# MCU.net
KiCad netlist of a schematic drawn in Altium Designer
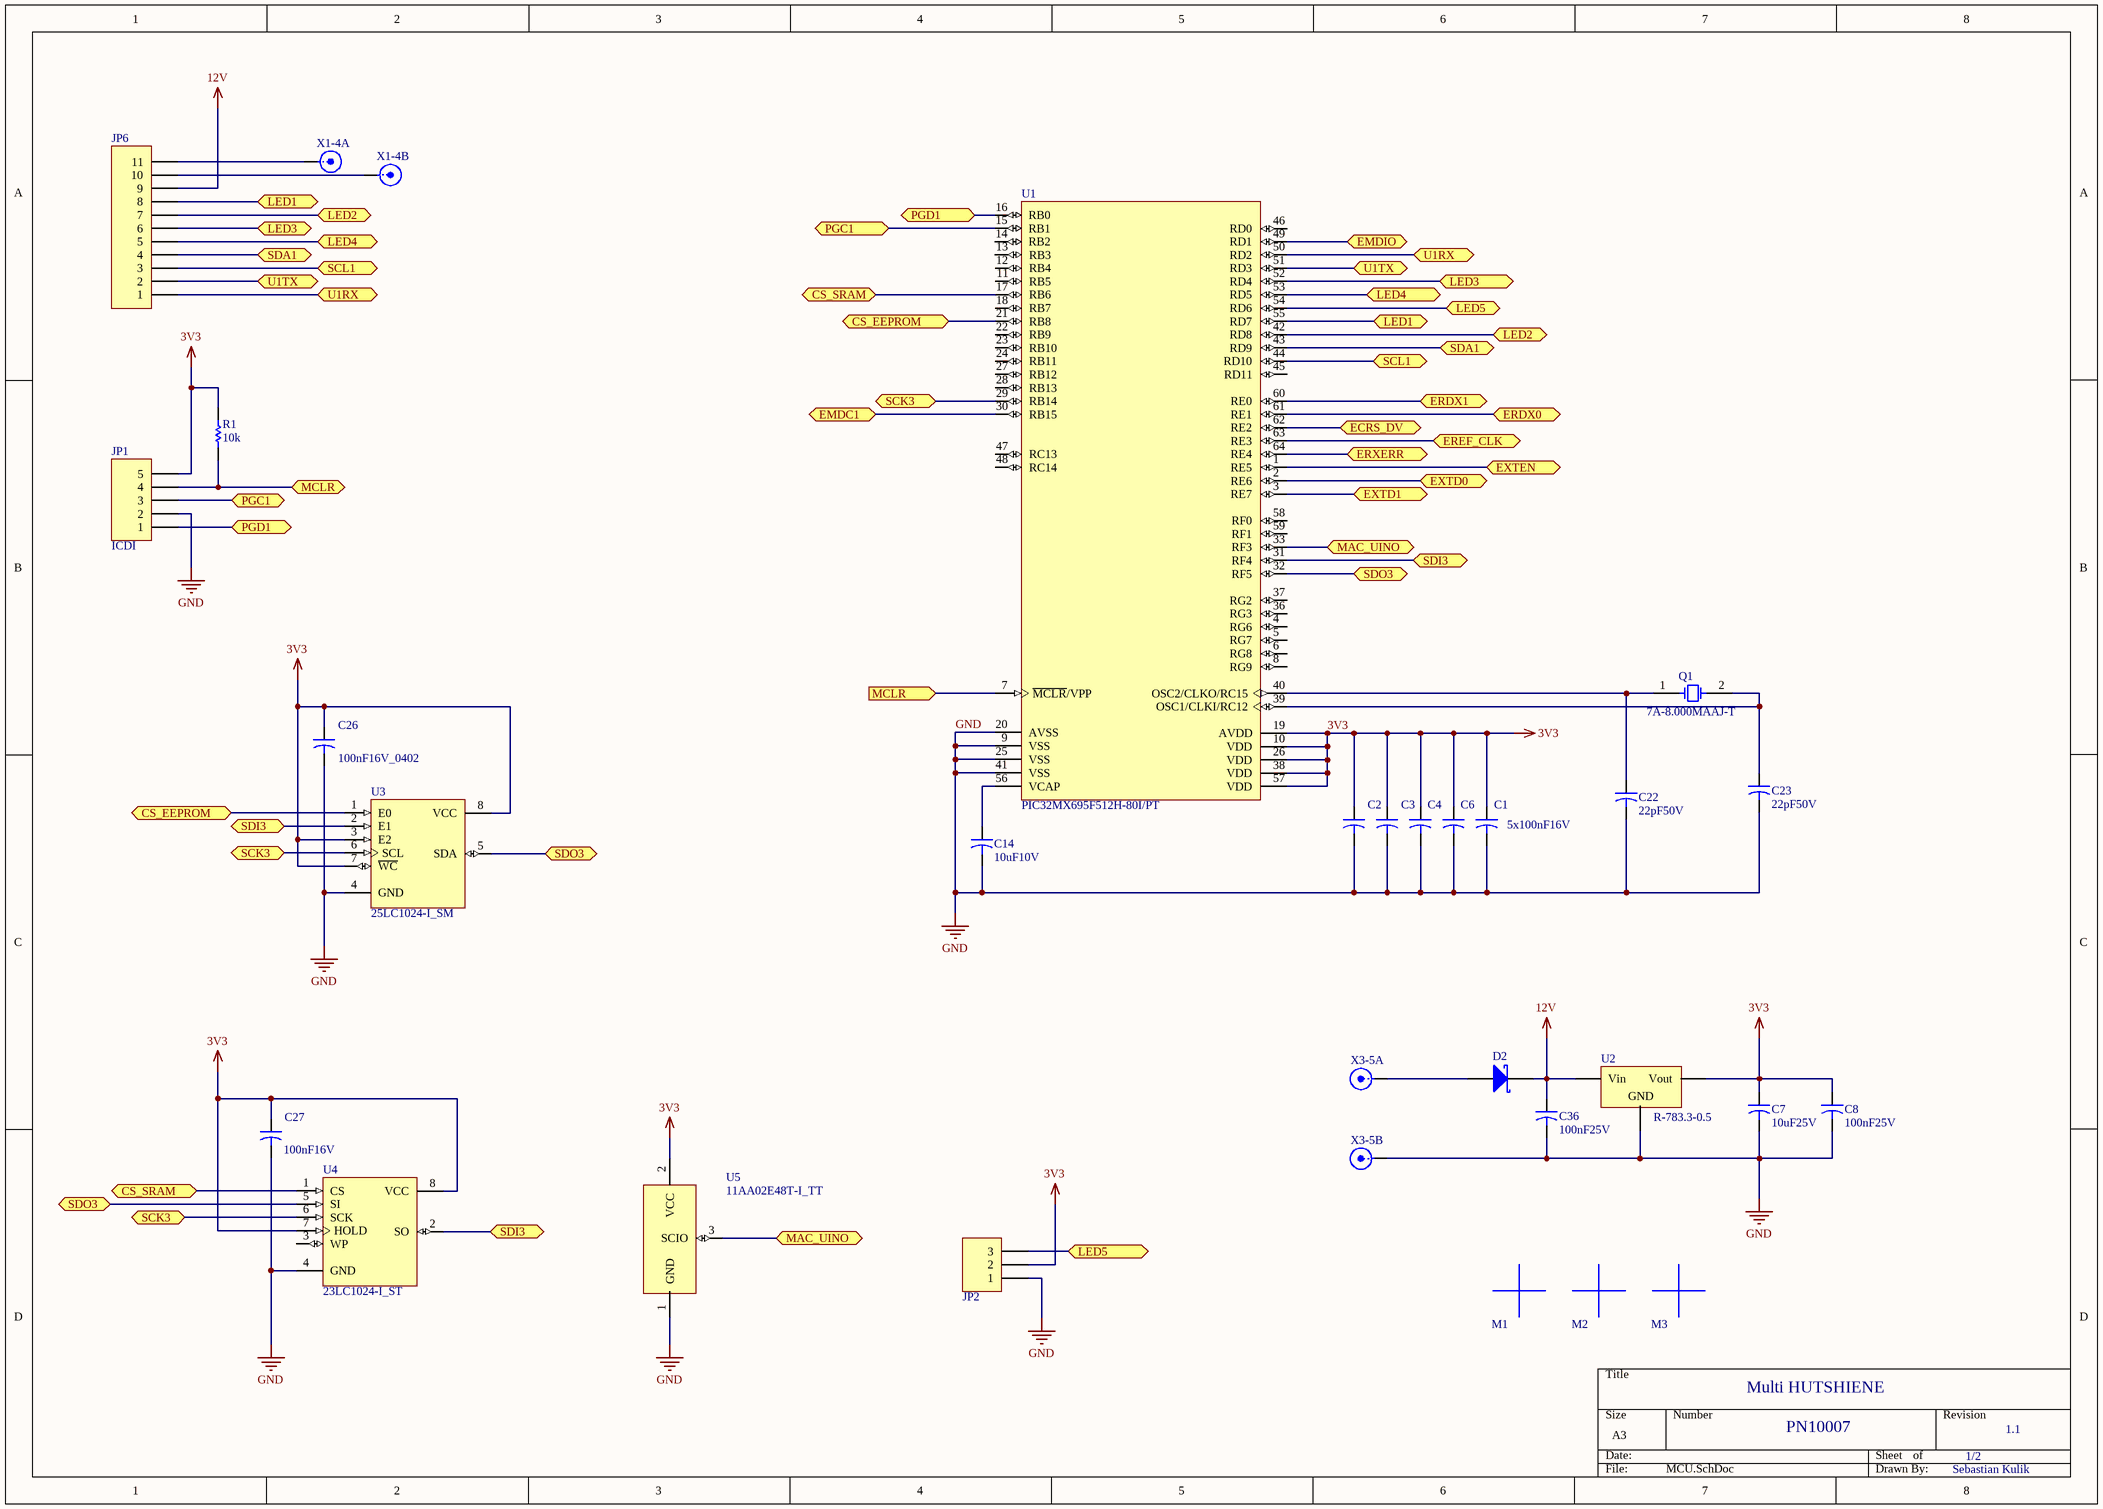
[diagram p0: MCU.SchDoc]

(export (version "E")
  (design (tool "Eeschema 10.0.6"))
  (components
    (comp (ref "C1")
      (value "100nF16V_0402")
      (footprint "C0402")
      (description "Capacitor")
      (fields (field (name "MANUFACTURER") "TDK") (field (name "PUBLISHER") "Sebastian Kulik"))
      (libsource (lib "Capacitors") (part "100nF16V_0402"))
    )
    (comp (ref "C2")
      (value "100nF16V_0402")
      (footprint "C0402")
      (description "Capacitor")
      (fields (field (name "MANUFACTURER") "TDK") (field (name "PUBLISHER") "Sebastian Kulik"))
      (libsource (lib "Capacitors") (part "100nF16V_0402"))
    )
    (comp (ref "C3")
      (value "100nF16V_0402")
      (footprint "C0402")
      (description "Capacitor")
      (fields (field (name "MANUFACTURER") "TDK") (field (name "PUBLISHER") "Sebastian Kulik"))
      (libsource (lib "Capacitors") (part "100nF16V_0402"))
    )
    (comp (ref "C4")
      (value "100nF16V_0402")
      (footprint "C0402")
      (description "Capacitor")
      (fields (field (name "MANUFACTURER") "TDK") (field (name "PUBLISHER") "Sebastian Kulik"))
      (libsource (lib "Capacitors") (part "100nF16V_0402"))
    )
    (comp (ref "C6")
      (value "100nF16V_0402")
      (footprint "C0402")
      (description "Capacitor")
      (fields (field (name "MANUFACTURER") "TDK") (field (name "PUBLISHER") "Sebastian Kulik"))
      (libsource (lib "Capacitors") (part "100nF16V_0402"))
    )
    (comp (ref "C7")
      (value "10uF25V")
      (footprint "C1210")
      (description "Capacitor")
      (fields
        (field (name "MANUFACTURER") "TDK")
        (field (name "Comment") "10uF25V_1210")
        (field (name "PUBLISHER") "Sebastian Kulik")
      )
      (libsource (lib "Capacitors") (part "10uF25V_1210"))
    )
    (comp (ref "C8")
      (value "100nF25V")
      (footprint "C0402")
      (description "AVX, X5R, 10%, 25V")
      (fields
        (field (name "MANUFACTURER") "AVX")
        (field (name "Comment") "100nF25V_0402")
        (field (name "PUBLISHER") "Sebastian Kulik")
      )
      (libsource (lib "Capacitors") (part "100nF25V_0402"))
    )
    (comp (ref "C14")
      (value "10uF10V")
      (footprint "C0603")
      (description "Capacitor")
      (fields
        (field (name "MANUFACTURER") "AVX")
        (field (name "Comment") "10uF10V_0603")
        (field (name "PUBLISHER") "Sebastian Kulik")
      )
      (libsource (lib "Capacitors") (part "10uF10V_0603"))
    )
    (comp (ref "C22")
      (value "22pF50V")
      (footprint "C0402")
      (description "Murata, GRM series, 50V")
      (fields
        (field (name "MANUFACTURER") "Murata")
        (field (name "Comment") "22pF50V_0402")
        (field (name "PUBLISHER") "Sebastian Kulik")
      )
      (libsource (lib "Capacitors") (part "22pF50V_0402"))
    )
    (comp (ref "C23")
      (value "22pF50V")
      (footprint "C0402")
      (description "Murata, GRM series, 50V")
      (fields
        (field (name "MANUFACTURER") "Murata")
        (field (name "Comment") "22pF50V_0402")
        (field (name "PUBLISHER") "Sebastian Kulik")
      )
      (libsource (lib "Capacitors") (part "22pF50V_0402"))
    )
    (comp (ref "C26")
      (value "100nF16V_0402")
      (footprint "C0402")
      (description "Capacitor")
      (fields (field (name "MANUFACTURER") "TDK") (field (name "PUBLISHER") "Sebastian Kulik"))
      (libsource (lib "Capacitors") (part "100nF16V_0402"))
    )
    (comp (ref "C27")
      (value "100nF16V")
      (footprint "C0402")
      (description "Capacitor")
      (fields
        (field (name "MANUFACTURER") "TDK")
        (field (name "Comment") "100nF16V_0402")
        (field (name "PUBLISHER") "Sebastian Kulik")
      )
      (libsource (lib "Capacitors") (part "100nF16V_0402"))
    )
    (comp (ref "C36")
      (value "100nF25V")
      (footprint "C0402")
      (description "AVX, X5R, 10%, 25V")
      (fields
        (field (name "MANUFACTURER") "AVX")
        (field (name "Comment") "100nF25V_0402")
        (field (name "PUBLISHER") "Sebastian Kulik")
      )
      (libsource (lib "Capacitors") (part "100nF25V_0402"))
    )
    (comp (ref "D2")
      (value "SD103AW-V-GS08")
      (footprint "SOD123")
      (description "Diode Schottky,2A,40V")
      (fields (field (name "MANUFACTURER") "Vishay") (field (name "PUBLISHER") "Sebastian Kulik"))
      (libsource (lib "Discrete") (part "SD103AW-V-GS08"))
    )
    (comp (ref "JP1")
      (value "ICDI")
      (footprint "HDR1X5-1.27")
      (description "Header, 5-Pin")
      (fields (field (name "PUBLISHER") "Sebastian Kulik"))
      (libsource (lib "Connectors") (part "ICDI"))
    )
    (comp (ref "JP2")
      (value "Header-3")
      (footprint "HDR1X3")
      (description "Header-3-Pin")
      (fields (field (name "PUBLISHER") "Sebastian Kulik"))
      (libsource (lib "Connectors") (part "Header-3"))
    )
    (comp (ref "JP6")
      (value "Header 11_2.54")
      (footprint "HDR1X11_2.54")
      (description "Header, 11-Pin")
      (fields (field (name "PUBLISHER") "Altium Limited"))
      (libsource (lib "Connectors") (part "Header 11_2.54"))
    )
    (comp (ref "M1") (value "Mark") (footprint "Mark-3mm") (libsource (lib "Symbols") (part "Mark")))
    (comp (ref "M2") (value "Mark") (footprint "Mark-3mm") (libsource (lib "Symbols") (part "Mark")))
    (comp (ref "M3") (value "Mark") (footprint "Mark-3mm") (libsource (lib "Symbols") (part "Mark")))
    (comp (ref "Q1")
      (value "7A-8.000MAAJ-T")
      (footprint "TXC_7A")
      (description "Crystal, 7A-8.000MAAJ-T")
      (fields (field (name "MANUFACTURER") "TXC") (field (name "PUBLISHER") "Sebastian Kulik"))
      (libsource (lib "Passives") (part "Crystal_8MHz"))
    )
    (comp (ref "R1")
      (value "10k")
      (footprint "R0402")
      (description "Vishay CRCW series, 125mW, 1%")
      (fields
        (field (name "MANUFACTURER") "Vishay")
        (field (name "Comment") "10k_0402")
        (field (name "PUBLISHER") "Sebastian Kulik")
      )
      (libsource (lib "Resistors") (part "10k_0402"))
    )
    (comp (ref "U1")
      (value "PIC32MX695F512H-80I/PT")
      (footprint "TQFP-64_N1")
      (fields (field (name "MANUFACTURER") "Microchip") (field (name "PUBLISHER") "Sebastian Kulik"))
      (libsource (lib "ICs") (part "PIC32MX695F512H-80I/PT"))
    )
    (comp (ref "U2")
      (value "R-783.3-0.5")
      (footprint "R-783_3-0_5")
      (description "Voltage Regulator")
      (fields (field (name "MANUFACTURER") "Recom") (field (name "PUBLISHER") "Sebastian Kulik"))
      (libsource (lib "ICs") (part "Recom-R-783_3-0_5"))
    )
    (comp (ref "U3")
      (value "25LC1024-I_SM")
      (footprint "SOP8_N")
      (description "1024 Kbit Serial SPI Bus EEPROM")
      (fields (field (name "MANUFACTURER") "Microchip") (field (name "PUBLISHER") "Sebastian Kulik"))
      (libsource (lib "ICs") (part "25LC1024-I_SM"))
    )
    (comp (ref "U4")
      (value "23LC1024-I_ST")
      (footprint "TSSOP8")
      (description "1 Mbit Serial  EEPROM")
      (fields (field (name "MANUFACTURER") "Microchip") (field (name "PUBLISHER") "Sebastian Kulik"))
      (libsource (lib "ICs") (part "23LC1024-I_ST"))
    )
    (comp (ref "U5")
      (value "11AA02E48T-I_TT")
      (footprint "SOT23_M")
      (description "2 kbit Serial  EEPROM")
      (fields (field (name "MANUFACTURER") "Microchip") (field (name "PUBLISHER") "Sebastian Kulik"))
      (libsource (lib "ICs") (part "11AA02E48T-I_TT"))
    )
    (comp (ref "X1-4")
      (value "Terminal-Wago_2")
      (footprint "WAGO-243-211")
      (description "Wago terminal-2")
      (fields (field (name "PUBLISHER") "Altium Limited"))
      (libsource (lib "Connectors") (part "Terminal-Wago_2"))
    )
    (comp (ref "X3-5")
      (value "Terminal-Wago_2")
      (footprint "WAGO-243-211")
      (description "Wago terminal-2")
      (fields (field (name "PUBLISHER") "Altium Limited"))
      (libsource (lib "") (part "Terminal-Wago_2_1"))
    )
  )
  (nets
    (net (code "1") (name "/CS_EEPROM") (class "Default")
      (node (ref "U1") (pin "21") (pinfunction "RB8_21") (pintype "bidirectional"))
      (node (ref "U3") (pin "1") (pinfunction "E0_1") (pintype "input"))
    )
    (net (code "2") (name "/CS_SRAM") (class "Default")
      (node (ref "U1") (pin "17") (pinfunction "RB6_17") (pintype "bidirectional"))
      (node (ref "U4") (pin "1") (pinfunction "CS_1") (pintype "input"))
    )
    (net (code "3") (name "/ECRS_DV") (class "Default")
      (node (ref "U1") (pin "62") (pinfunction "RE2_62") (pintype "bidirectional"))
    )
    (net (code "4") (name "/EMDC1") (class "Default")
      (node (ref "U1") (pin "30") (pinfunction "RB15_30") (pintype "bidirectional"))
    )
    (net (code "5") (name "/EMDIO") (class "Default")
      (node (ref "U1") (pin "49") (pinfunction "RD1_49") (pintype "bidirectional"))
    )
    (net (code "6") (name "/ERDX0") (class "Default")
      (node (ref "U1") (pin "61") (pinfunction "RE1_61") (pintype "bidirectional"))
    )
    (net (code "7") (name "/ERDX1") (class "Default")
      (node (ref "U1") (pin "60") (pinfunction "RE0_60") (pintype "bidirectional"))
    )
    (net (code "8") (name "/EREF_CLK") (class "Default")
      (node (ref "U1") (pin "63") (pinfunction "RE3_63") (pintype "bidirectional"))
    )
    (net (code "9") (name "/ERXERR") (class "Default")
      (node (ref "U1") (pin "64") (pinfunction "RE4_64") (pintype "bidirectional"))
    )
    (net (code "10") (name "/EXTD0") (class "Default")
      (node (ref "U1") (pin "2") (pinfunction "RE6_2") (pintype "bidirectional"))
    )
    (net (code "11") (name "/EXTD1") (class "Default")
      (node (ref "U1") (pin "3") (pinfunction "RE7_3") (pintype "bidirectional"))
    )
    (net (code "12") (name "/EXTEN") (class "Default")
      (node (ref "U1") (pin "1") (pinfunction "RE5_1") (pintype "bidirectional"))
    )
    (net (code "13") (name "/LED1") (class "Default")
      (node (ref "JP6") (pin "8") (pinfunction "8_8") (pintype "passive"))
      (node (ref "U1") (pin "55") (pinfunction "RD7_55") (pintype "bidirectional"))
    )
    (net (code "14") (name "/LED2") (class "Default")
      (node (ref "JP6") (pin "7") (pinfunction "7_7") (pintype "passive"))
      (node (ref "U1") (pin "42") (pinfunction "RD8_42") (pintype "bidirectional"))
    )
    (net (code "15") (name "/LED3") (class "Default")
      (node (ref "JP6") (pin "6") (pinfunction "6_6") (pintype "passive"))
      (node (ref "U1") (pin "52") (pinfunction "RD4_52") (pintype "bidirectional"))
    )
    (net (code "16") (name "/LED4") (class "Default")
      (node (ref "JP6") (pin "5") (pinfunction "5_5") (pintype "passive"))
      (node (ref "U1") (pin "53") (pinfunction "RD5_53") (pintype "bidirectional"))
    )
    (net (code "17") (name "/LED5") (class "Default")
      (node (ref "JP2") (pin "3") (pinfunction "3_3") (pintype "passive"))
      (node (ref "U1") (pin "54") (pinfunction "RD6_54") (pintype "bidirectional"))
    )
    (net (code "18") (name "/MAC_UINO") (class "Default")
      (node (ref "U1") (pin "33") (pinfunction "RF3_33") (pintype "bidirectional"))
      (node (ref "U5") (pin "3") (pinfunction "SCIO_3") (pintype "bidirectional"))
    )
    (net (code "19") (name "/MCLR") (class "Default")
      (node (ref "JP1") (pin "4") (pinfunction "4_4") (pintype "passive"))
      (node (ref "R1") (pin "1") (pinfunction "1_1") (pintype "passive"))
      (node (ref "U1") (pin "7") (pinfunction "~{MCLR}/VPP_7") (pintype "input"))
    )
    (net (code "20") (name "/PGC1") (class "Default")
      (node (ref "JP1") (pin "3") (pinfunction "3_3") (pintype "passive"))
      (node (ref "U1") (pin "15") (pinfunction "RB1_15") (pintype "bidirectional"))
    )
    (net (code "21") (name "/PGD1") (class "Default")
      (node (ref "JP1") (pin "1") (pinfunction "1_1") (pintype "passive"))
      (node (ref "U1") (pin "16") (pinfunction "RB0_16") (pintype "bidirectional"))
    )
    (net (code "22") (name "/SCK3") (class "Default")
      (node (ref "U1") (pin "29") (pinfunction "RB14_29") (pintype "bidirectional"))
      (node (ref "U3") (pin "6") (pinfunction "SCL_6") (pintype "input"))
      (node (ref "U4") (pin "6") (pinfunction "SCK_6") (pintype "input"))
    )
    (net (code "23") (name "/SCL1") (class "Default")
      (node (ref "JP6") (pin "3") (pinfunction "3_3") (pintype "passive"))
      (node (ref "U1") (pin "44") (pinfunction "RD10_44") (pintype "bidirectional"))
    )
    (net (code "24") (name "/SDA1") (class "Default")
      (node (ref "JP6") (pin "4") (pinfunction "4_4") (pintype "passive"))
      (node (ref "U1") (pin "43") (pinfunction "RD9_43") (pintype "bidirectional"))
    )
    (net (code "25") (name "/SDI3") (class "Default")
      (node (ref "U1") (pin "31") (pinfunction "RF4_31") (pintype "bidirectional"))
      (node (ref "U3") (pin "2") (pinfunction "E1_2") (pintype "input"))
      (node (ref "U4") (pin "2") (pinfunction "SO_2") (pintype "bidirectional"))
    )
    (net (code "26") (name "/SDO3") (class "Default")
      (node (ref "U1") (pin "32") (pinfunction "RF5_32") (pintype "bidirectional"))
      (node (ref "U3") (pin "5") (pinfunction "SDA_5") (pintype "bidirectional"))
      (node (ref "U4") (pin "5") (pinfunction "SI_5") (pintype "input"))
    )
    (net (code "27") (name "/U1RX") (class "Default")
      (node (ref "JP6") (pin "1") (pinfunction "1_1") (pintype "passive"))
      (node (ref "U1") (pin "50") (pinfunction "RD2_50") (pintype "bidirectional"))
    )
    (net (code "28") (name "/U1TX") (class "Default")
      (node (ref "JP6") (pin "2") (pinfunction "2_2") (pintype "passive"))
      (node (ref "U1") (pin "51") (pinfunction "RD3_51") (pintype "bidirectional"))
    )
    (net (code "29") (name "3V3") (class "Default")
      (node (ref "C1") (pin "1") (pinfunction "1_1") (pintype "passive"))
      (node (ref "C2") (pin "1") (pinfunction "1_1") (pintype "passive"))
      (node (ref "C26") (pin "1") (pinfunction "1_1") (pintype "passive"))
      (node (ref "C27") (pin "1") (pinfunction "1_1") (pintype "passive"))
      (node (ref "C3") (pin "1") (pinfunction "1_1") (pintype "passive"))
      (node (ref "C4") (pin "1") (pinfunction "1_1") (pintype "passive"))
      (node (ref "C6") (pin "1") (pinfunction "1_1") (pintype "passive"))
      (node (ref "C7") (pin "1") (pinfunction "1_1") (pintype "passive"))
      (node (ref "C8") (pin "1") (pinfunction "1_1") (pintype "passive"))
      (node (ref "JP1") (pin "5") (pinfunction "5_5") (pintype "passive"))
      (node (ref "JP2") (pin "2") (pinfunction "2_2") (pintype "passive"))
      (node (ref "R1") (pin "2") (pinfunction "2_2") (pintype "passive"))
      (node (ref "U1") (pin "10") (pinfunction "VDD_10") (pintype "power_in"))
      (node (ref "U1") (pin "19") (pinfunction "AVDD_19") (pintype "power_in"))
      (node (ref "U1") (pin "26") (pinfunction "VDD_26") (pintype "power_in"))
      (node (ref "U1") (pin "38") (pinfunction "VDD_38") (pintype "power_in"))
      (node (ref "U1") (pin "57") (pinfunction "VDD_57") (pintype "power_in"))
      (node (ref "U2") (pin "3") (pinfunction "Vout_3") (pintype "passive"))
      (node (ref "U3") (pin "3") (pinfunction "E2_3") (pintype "input"))
      (node (ref "U3") (pin "7") (pinfunction "~{WC}_7") (pintype "bidirectional"))
      (node (ref "U3") (pin "8") (pinfunction "VCC_8") (pintype "power_in"))
      (node (ref "U4") (pin "7") (pinfunction "HOLD_7") (pintype "input"))
      (node (ref "U4") (pin "8") (pinfunction "VCC_8") (pintype "power_in"))
      (node (ref "U5") (pin "2") (pinfunction "VCC_2") (pintype "power_in"))
    )
    (net (code "30") (name "12V") (class "Default")
      (node (ref "C36") (pin "1") (pinfunction "1_1") (pintype "passive"))
      (node (ref "D2") (pin "1") (pinfunction "K_1") (pintype "passive"))
      (node (ref "JP6") (pin "9") (pinfunction "9_9") (pintype "passive"))
      (node (ref "U2") (pin "1") (pinfunction "Vin_1") (pintype "passive"))
    )
    (net (code "31") (name "GND") (class "Default")
      (node (ref "C1") (pin "2") (pinfunction "2_2") (pintype "passive"))
      (node (ref "C14") (pin "2") (pinfunction "2_2") (pintype "passive"))
      (node (ref "C2") (pin "2") (pinfunction "2_2") (pintype "passive"))
      (node (ref "C22") (pin "2") (pinfunction "2_2") (pintype "passive"))
      (node (ref "C23") (pin "2") (pinfunction "2_2") (pintype "passive"))
      (node (ref "C26") (pin "2") (pinfunction "2_2") (pintype "passive"))
      (node (ref "C27") (pin "2") (pinfunction "2_2") (pintype "passive"))
      (node (ref "C3") (pin "2") (pinfunction "2_2") (pintype "passive"))
      (node (ref "C36") (pin "2") (pinfunction "2_2") (pintype "passive"))
      (node (ref "C4") (pin "2") (pinfunction "2_2") (pintype "passive"))
      (node (ref "C6") (pin "2") (pinfunction "2_2") (pintype "passive"))
      (node (ref "C7") (pin "2") (pinfunction "2_2") (pintype "passive"))
      (node (ref "C8") (pin "2") (pinfunction "2_2") (pintype "passive"))
      (node (ref "JP1") (pin "2") (pinfunction "2_2") (pintype "passive"))
      (node (ref "JP2") (pin "1") (pinfunction "1_1") (pintype "passive"))
      (node (ref "U1") (pin "20") (pinfunction "AVSS_20") (pintype "power_in"))
      (node (ref "U1") (pin "25") (pinfunction "VSS_25") (pintype "power_in"))
      (node (ref "U1") (pin "41") (pinfunction "VSS_41") (pintype "power_in"))
      (node (ref "U1") (pin "9") (pinfunction "VSS_9") (pintype "power_in"))
      (node (ref "U2") (pin "2") (pinfunction "GND_2") (pintype "passive"))
      (node (ref "U3") (pin "4") (pinfunction "GND_4") (pintype "power_in"))
      (node (ref "U4") (pin "4") (pinfunction "GND_4") (pintype "power_in"))
      (node (ref "U5") (pin "1") (pinfunction "GND_1") (pintype "power_in"))
      (node (ref "X3-5") (pin "2") (pinfunction "Y_2") (pintype "passive"))
    )
    (net (code "32") (name "Net-(D2-A)") (class "Default")
      (node (ref "D2") (pin "2") (pinfunction "A_2") (pintype "passive"))
      (node (ref "X3-5") (pin "1") (pinfunction "X_1") (pintype "passive"))
    )
    (net (code "33") (name "Net-(Q1-E{slash}D)") (class "Default")
      (node (ref "C22") (pin "1") (pinfunction "1_1") (pintype "passive"))
      (node (ref "Q1") (pin "1") (pinfunction "E/D_1") (pintype "passive"))
      (node (ref "U1") (pin "40") (pinfunction "OSC2/CLKO/RC15_40") (pintype "output"))
    )
    (net (code "34") (name "Net-(Q1-GND)") (class "Default")
      (node (ref "C23") (pin "1") (pinfunction "1_1") (pintype "passive"))
      (node (ref "Q1") (pin "2") (pinfunction "GND_2") (pintype "passive"))
      (node (ref "U1") (pin "39") (pinfunction "OSC1/CLKI/RC12_39") (pintype "bidirectional"))
    )
    (net (code "35") (name "Net-(U1-VCAP)") (class "Default")
      (node (ref "C14") (pin "1") (pinfunction "1_1") (pintype "passive"))
      (node (ref "U1") (pin "56") (pinfunction "VCAP_56") (pintype "power_in"))
    )
    (net (code "36") (name "Net-(X1-4A-X)") (class "Default")
      (node (ref "JP6") (pin "11") (pinfunction "11_11") (pintype "passive"))
      (node (ref "X1-4") (pin "1") (pinfunction "X_1") (pintype "passive"))
    )
    (net (code "37") (name "Net-(X1-4B-Y)") (class "Default")
      (node (ref "JP6") (pin "10") (pinfunction "10_10") (pintype "passive"))
      (node (ref "X1-4") (pin "2") (pinfunction "Y_2") (pintype "passive"))
    )
    (net (code "38") (name "unconnected-(U1-RB2-Pad14)") (class "Default")
      (node (ref "U1") (pin "14") (pinfunction "RB2_14") (pintype "bidirectional"))
    )
    (net (code "39") (name "unconnected-(U1-RB3-Pad13)") (class "Default")
      (node (ref "U1") (pin "13") (pinfunction "RB3_13") (pintype "bidirectional"))
    )
    (net (code "40") (name "unconnected-(U1-RB4-Pad12)") (class "Default")
      (node (ref "U1") (pin "12") (pinfunction "RB4_12") (pintype "bidirectional"))
    )
    (net (code "41") (name "unconnected-(U1-RB5-Pad11)") (class "Default")
      (node (ref "U1") (pin "11") (pinfunction "RB5_11") (pintype "bidirectional"))
    )
    (net (code "42") (name "unconnected-(U1-RB7-Pad18)") (class "Default")
      (node (ref "U1") (pin "18") (pinfunction "RB7_18") (pintype "bidirectional"))
    )
    (net (code "43") (name "unconnected-(U1-RB9-Pad22)") (class "Default")
      (node (ref "U1") (pin "22") (pinfunction "RB9_22") (pintype "bidirectional"))
    )
    (net (code "44") (name "unconnected-(U1-RB10-Pad23)") (class "Default")
      (node (ref "U1") (pin "23") (pinfunction "RB10_23") (pintype "bidirectional"))
    )
    (net (code "45") (name "unconnected-(U1-RB11-Pad24)") (class "Default")
      (node (ref "U1") (pin "24") (pinfunction "RB11_24") (pintype "bidirectional"))
    )
    (net (code "46") (name "unconnected-(U1-RB12-Pad27)") (class "Default")
      (node (ref "U1") (pin "27") (pinfunction "RB12_27") (pintype "bidirectional"))
    )
    (net (code "47") (name "unconnected-(U1-RB13-Pad28)") (class "Default")
      (node (ref "U1") (pin "28") (pinfunction "RB13_28") (pintype "bidirectional"))
    )
    (net (code "48") (name "unconnected-(U1-RC13-Pad47)") (class "Default")
      (node (ref "U1") (pin "47") (pinfunction "RC13_47") (pintype "bidirectional"))
    )
    (net (code "49") (name "unconnected-(U1-RC14-Pad48)") (class "Default")
      (node (ref "U1") (pin "48") (pinfunction "RC14_48") (pintype "bidirectional"))
    )
    (net (code "50") (name "unconnected-(U1-RD0-Pad46)") (class "Default")
      (node (ref "U1") (pin "46") (pinfunction "RD0_46") (pintype "bidirectional"))
    )
    (net (code "51") (name "unconnected-(U1-RD11-Pad45)") (class "Default")
      (node (ref "U1") (pin "45") (pinfunction "RD11_45") (pintype "bidirectional"))
    )
    (net (code "52") (name "unconnected-(U1-RF0-Pad58)") (class "Default")
      (node (ref "U1") (pin "58") (pinfunction "RF0_58") (pintype "bidirectional"))
    )
    (net (code "53") (name "unconnected-(U1-RF1-Pad59)") (class "Default")
      (node (ref "U1") (pin "59") (pinfunction "RF1_59") (pintype "bidirectional"))
    )
    (net (code "54") (name "unconnected-(U1-RG2-Pad37)") (class "Default")
      (node (ref "U1") (pin "37") (pinfunction "RG2_37") (pintype "bidirectional"))
    )
    (net (code "55") (name "unconnected-(U1-RG3-Pad36)") (class "Default")
      (node (ref "U1") (pin "36") (pinfunction "RG3_36") (pintype "bidirectional"))
    )
    (net (code "56") (name "unconnected-(U1-RG6-Pad4)") (class "Default")
      (node (ref "U1") (pin "4") (pinfunction "RG6_4") (pintype "bidirectional"))
    )
    (net (code "57") (name "unconnected-(U1-RG7-Pad5)") (class "Default")
      (node (ref "U1") (pin "5") (pinfunction "RG7_5") (pintype "bidirectional"))
    )
    (net (code "58") (name "unconnected-(U1-RG8-Pad6)") (class "Default")
      (node (ref "U1") (pin "6") (pinfunction "RG8_6") (pintype "bidirectional"))
    )
    (net (code "59") (name "unconnected-(U1-RG9-Pad8)") (class "Default")
      (node (ref "U1") (pin "8") (pinfunction "RG9_8") (pintype "bidirectional"))
    )
    (net (code "60") (name "unconnected-(U4-WP-Pad3)") (class "Default")
      (node (ref "U4") (pin "3") (pinfunction "WP_3") (pintype "bidirectional"))
    )
  )
)
